# CPU_EX.net
KiCad netlist of a schematic drawn in Altium Designer
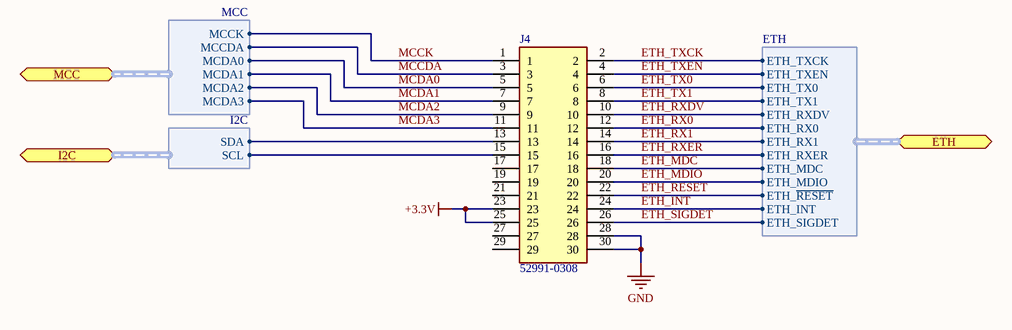
[diagram p0: CPU_EX.SchDoc]

(export (version "E")
  (design (tool "Eeschema 10.0.6"))
  (components
    (comp (ref "J4")
      (value "52991-0308")
      (footprint "529910308")
      (description "Connector")
      (libsource (lib "ModularPayload") (part "52991-0308"))
    )
  )
  (nets
    (net (code "4") (name "+3.3V") (class "Default")
      (node (ref "J4") (pin "23") (pinfunction "23_23") (pintype "passive"))
      (node (ref "J4") (pin "25") (pinfunction "25_25") (pintype "passive"))
    )
    (net (code "5") (name "/ETH_INT") (class "Default")
      (node (ref "J4") (pin "24") (pinfunction "24_24") (pintype "passive"))
    )
    (net (code "6") (name "/ETH_MDC") (class "Default")
      (node (ref "J4") (pin "18") (pinfunction "18_18") (pintype "passive"))
    )
    (net (code "7") (name "/ETH_MDIO") (class "Default")
      (node (ref "J4") (pin "20") (pinfunction "20_20") (pintype "passive"))
    )
    (net (code "8") (name "/ETH_RX0") (class "Default")
      (node (ref "J4") (pin "12") (pinfunction "12_12") (pintype "passive"))
    )
    (net (code "9") (name "/ETH_RX1") (class "Default")
      (node (ref "J4") (pin "14") (pinfunction "14_14") (pintype "passive"))
    )
    (net (code "10") (name "/ETH_RXDV") (class "Default")
      (node (ref "J4") (pin "10") (pinfunction "10_10") (pintype "passive"))
    )
    (net (code "11") (name "/ETH_RXER") (class "Default")
      (node (ref "J4") (pin "16") (pinfunction "16_16") (pintype "passive"))
    )
    (net (code "12") (name "/ETH_SIGDET") (class "Default")
      (node (ref "J4") (pin "26") (pinfunction "26_26") (pintype "passive"))
    )
    (net (code "13") (name "/ETH_TX0") (class "Default")
      (node (ref "J4") (pin "6") (pinfunction "6_6") (pintype "passive"))
    )
    (net (code "14") (name "/ETH_TX1") (class "Default")
      (node (ref "J4") (pin "8") (pinfunction "8_8") (pintype "passive"))
    )
    (net (code "15") (name "/ETH_TXCK") (class "Default")
      (node (ref "J4") (pin "2") (pinfunction "2_2") (pintype "passive"))
    )
    (net (code "16") (name "/ETH_TXEN") (class "Default")
      (node (ref "J4") (pin "4") (pinfunction "4_4") (pintype "passive"))
    )
    (net (code "17") (name "/ETH_~{RESET}") (class "Default")
      (node (ref "J4") (pin "22") (pinfunction "22_22") (pintype "passive"))
    )
    (net (code "18") (name "/MCCDA") (class "Default")
      (node (ref "J4") (pin "3") (pinfunction "3_3") (pintype "passive"))
    )
    (net (code "19") (name "/MCCK") (class "Default")
      (node (ref "J4") (pin "1") (pinfunction "1_1") (pintype "passive"))
    )
    (net (code "20") (name "/MCDA0") (class "Default")
      (node (ref "J4") (pin "5") (pinfunction "5_5") (pintype "passive"))
    )
    (net (code "21") (name "/MCDA1") (class "Default")
      (node (ref "J4") (pin "7") (pinfunction "7_7") (pintype "passive"))
    )
    (net (code "22") (name "/MCDA2") (class "Default")
      (node (ref "J4") (pin "9") (pinfunction "9_9") (pintype "passive"))
    )
    (net (code "23") (name "/MCDA3") (class "Default")
      (node (ref "J4") (pin "11") (pinfunction "11_11") (pintype "passive"))
    )
    (net (code "24") (name "/SCL") (class "Default")
      (node (ref "J4") (pin "15") (pinfunction "15_15") (pintype "passive"))
    )
    (net (code "25") (name "/SDA") (class "Default")
      (node (ref "J4") (pin "13") (pinfunction "13_13") (pintype "passive"))
    )
    (net (code "29") (name "GND") (class "Default")
      (node (ref "J4") (pin "28") (pinfunction "28_28") (pintype "passive"))
      (node (ref "J4") (pin "30") (pinfunction "30_30") (pintype "passive"))
    )
    (net (code "30") (name "unconnected-(J4-Pad17)") (class "Default")
      (node (ref "J4") (pin "17") (pinfunction "17_17") (pintype "passive"))
    )
    (net (code "31") (name "unconnected-(J4-Pad19)") (class "Default")
      (node (ref "J4") (pin "19") (pinfunction "19_19") (pintype "passive"))
    )
    (net (code "32") (name "unconnected-(J4-Pad21)") (class "Default")
      (node (ref "J4") (pin "21") (pinfunction "21_21") (pintype "passive"))
    )
    (net (code "33") (name "unconnected-(J4-Pad27)") (class "Default")
      (node (ref "J4") (pin "27") (pinfunction "27_27") (pintype "passive"))
    )
    (net (code "34") (name "unconnected-(J4-Pad29)") (class "Default")
      (node (ref "J4") (pin "29") (pinfunction "29_29") (pintype "passive"))
    )
  )
)
